# inverter_board.net
KiCad netlist of a schematic drawn in Altium Designer
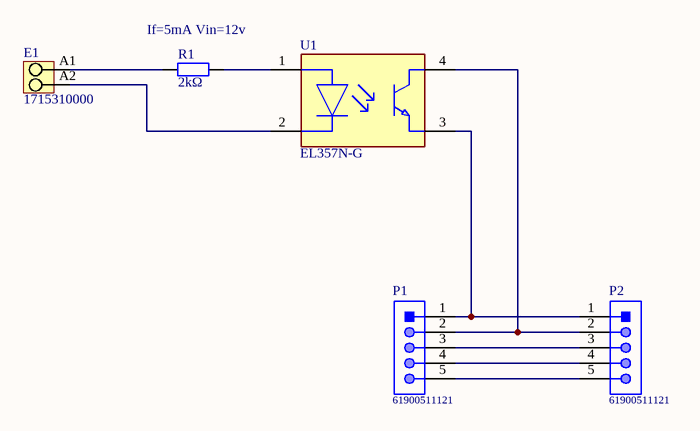
[diagram p0: inverter_board.SchDoc]

(export (version "E")
  (design (tool "Eeschema 10.0.6"))
  (components
    (comp (ref "E1")
      (value "1715310000")
      (footprint "LM_5_00_90_02")
      (description "OMNIMATE Signal - series LM")
      (fields (field (name "MANUFACTURER") "Weidmueller"))
      (libsource (lib "Altium Content Vault") (part "Terminal_02_1x02"))
    )
    (comp (ref "P1")
      (value "61900511121")
      (footprint "61900511121")
      (description "Male Locking Header WR-WTB, THT, Vertical, pitch 2.54 mm, 1 x 5 position")
      (fields (field (name "MANUFACTURER") "Wurth Elektronik") (field (name "PUBLISHER") "WurthElektronik"))
      (libsource (lib "Altium Content Vault") (part "WE-CN-1P-M-R5"))
    )
    (comp (ref "P2")
      (value "61900511121")
      (footprint "61900511121")
      (description "Male Locking Header WR-WTB, THT, Vertical, pitch 2.54 mm, 1 x 5 position")
      (fields (field (name "MANUFACTURER") "Wurth Elektronik") (field (name "PUBLISHER") "WurthElektronik"))
      (libsource (lib "") (part "WE-CN-1P-M-R5_1"))
    )
    (comp (ref "R1")
      (value "2kΩ")
      (footprint "RES_0805")
      (description "Res Thick Film 0805 100K Ohm 1% 0.125W(1/8W) ±100ppm/°C Molded SMD Punched Carrier T/R")
      (fields
        (field (name "MANUFACTURER") "Panasonic")
        (field (name "MANUFACTURER PART NUMBER") "ERJ-6ENF1003V")
      )
      (libsource (lib "integrated_library") (part "RES_100kohm_0805"))
    )
    (comp (ref "U1")
      (value "EL357N-G")
      (footprint "SOP-4_4mm")
      (libsource (lib "integrated_library") (part "OPTOCOUPLER_EL357N-G"))
    )
  )
  (nets
    (net (code "1") (name "Net-(E1-PadA1)") (class "Default")
      (node (ref "E1") (pin "A1") (pinfunction "A1_A1") (pintype "passive"))
      (node (ref "R1") (pin "1") (pinfunction "1_1") (pintype "passive"))
    )
    (net (code "2") (name "Net-(E1-PadA2)") (class "Default")
      (node (ref "E1") (pin "A2") (pinfunction "A2_A2") (pintype "passive"))
      (node (ref "U1") (pin "2") (pinfunction "C_2") (pintype "passive"))
    )
    (net (code "3") (name "Net-(P1-Pad2)") (class "Default")
      (node (ref "P1") (pin "2") (pinfunction "2_2") (pintype "passive"))
      (node (ref "P2") (pin "2") (pinfunction "2_2") (pintype "passive"))
      (node (ref "U1") (pin "4") (pinfunction "C_4") (pintype "passive"))
    )
    (net (code "4") (name "Net-(P1-Pad3)") (class "Default")
      (node (ref "P1") (pin "3") (pinfunction "3_3") (pintype "passive"))
      (node (ref "P2") (pin "3") (pinfunction "3_3") (pintype "passive"))
    )
    (net (code "5") (name "Net-(P1-Pad4)") (class "Default")
      (node (ref "P1") (pin "4") (pinfunction "4_4") (pintype "passive"))
      (node (ref "P2") (pin "4") (pinfunction "4_4") (pintype "passive"))
    )
    (net (code "6") (name "Net-(P1-Pad5)") (class "Default")
      (node (ref "P1") (pin "5") (pinfunction "5_5") (pintype "passive"))
      (node (ref "P2") (pin "5") (pinfunction "5_5") (pintype "passive"))
    )
    (net (code "7") (name "Net-(U1-A)") (class "Default")
      (node (ref "R1") (pin "2") (pinfunction "2_2") (pintype "passive"))
      (node (ref "U1") (pin "1") (pinfunction "A_1") (pintype "passive"))
    )
    (net (code "8") (name "Net-(U1-E)") (class "Default")
      (node (ref "P1") (pin "1") (pinfunction "1_1") (pintype "passive"))
      (node (ref "P2") (pin "1") (pinfunction "1_1") (pintype "passive"))
      (node (ref "U1") (pin "3") (pinfunction "E_3") (pintype "passive"))
    )
  )
)
